# SMPS-5V.net
KiCad netlist of a schematic drawn in Altium Designer
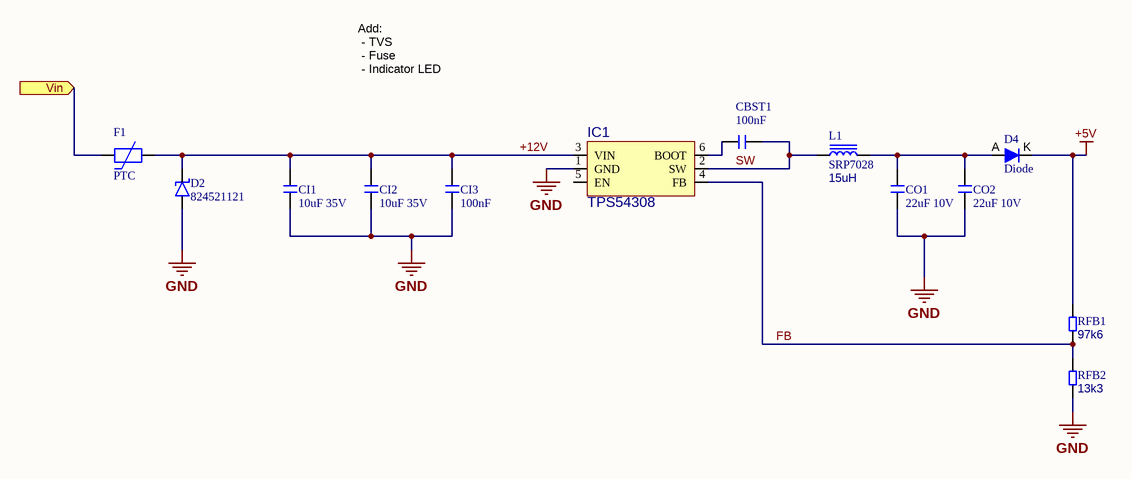
[diagram p0: SMPS-5V.SchDoc]

(export (version "E")
  (design (tool "Eeschema 10.0.6"))
  (components
    (comp (ref "CBST1")
      (value "100nF")
      (footprint "C0603_N")
      (description "Capacitor MLCC")
      (fields
        (field (name "MANUFACTURER") "Yageo")
        (field (name "MANUFACTURER PART NUMBER") "CC0603KRX7R9BB104")
      )
      (libsource (lib "wes") (part "Capacitor"))
    )
    (comp (ref "CI1")
      (value "10uF 35V")
      (footprint "C1210_N")
      (description "Capacitor MLCC")
      (fields
        (field (name "MANUFACTURER") "Yageo")
        (field (name "MANUFACTURER PART NUMBER") "CC0603KRX7R9BB104")
      )
      (libsource (lib "wes") (part "Capacitor"))
    )
    (comp (ref "CI2")
      (value "10uF 35V")
      (footprint "C1210_N")
      (description "Capacitor MLCC")
      (fields
        (field (name "MANUFACTURER") "Yageo")
        (field (name "MANUFACTURER PART NUMBER") "CC0603KRX7R9BB104")
      )
      (libsource (lib "wes") (part "Capacitor"))
    )
    (comp (ref "CI3")
      (value "100nF")
      (footprint "C0603_N")
      (description "Capacitor MLCC")
      (fields
        (field (name "MANUFACTURER") "Yageo")
        (field (name "MANUFACTURER PART NUMBER") "CC0603KRX7R9BB104")
      )
      (libsource (lib "wes") (part "Capacitor"))
    )
    (comp (ref "CO1")
      (value "22uF 10V")
      (footprint "C1210_N")
      (description "Capacitor MLCC")
      (fields
        (field (name "MANUFACTURER") "Yageo")
        (field (name "MANUFACTURER PART NUMBER") "CC0603KRX7R9BB104")
      )
      (libsource (lib "wes") (part "Capacitor"))
    )
    (comp (ref "CO2")
      (value "22uF 10V")
      (footprint "C1210_N")
      (description "Capacitor MLCC")
      (fields
        (field (name "MANUFACTURER") "Yageo")
        (field (name "MANUFACTURER PART NUMBER") "CC0603KRX7R9BB104")
      )
      (libsource (lib "wes") (part "Capacitor"))
    )
    (comp (ref "D2") (value "824521121") (footprint "DO214AC SMA") (libsource (lib "wes") (part "TVS")))
    (comp (ref "D4") (value "Diode") (footprint "SOD323F") (libsource (lib "wes") (part "Diode")))
    (comp (ref "F1")
      (value "PTC")
      (footprint "C1206_N")
      (description "PTC, Resettable Fuse")
      (libsource (lib "wes") (part "PTC"))
    )
    (comp (ref "IC1")
      (value "TPS54308")
      (footprint "SOT23")
      (description "Buck Converter")
      (libsource (lib "wes") (part "TPS54308"))
    )
    (comp (ref "L1")
      (value "SRP7028")
      (footprint "Inductor SRP7028")
      (fields (field (name "ALTIUM_VALUE") "15uH"))
      (libsource (lib "wes") (part "Inductor"))
    )
    (comp (ref "RFB1")
      (value "97k6")
      (footprint "R0603")
      (fields (field (name "Comment") "100k") (field (name "PUBLISHER") "Altium Limited"))
      (libsource (lib "wes") (part "Resistor"))
    )
    (comp (ref "RFB2")
      (value "13k3")
      (footprint "R0603")
      (fields (field (name "Comment") "13k5") (field (name "PUBLISHER") "Altium Limited"))
      (libsource (lib "wes") (part "Resistor"))
    )
  )
  (nets
    (net (code "1") (name "+5V") (class "Default")
      (node (ref "D4") (pin "K") (pinfunction "K_K") (pintype "passive"))
      (node (ref "RFB1") (pin "2") (pinfunction "2_2") (pintype "passive"))
    )
    (net (code "2") (name "/+12V") (class "Default")
      (node (ref "CI1") (pin "1") (pintype "passive"))
      (node (ref "CI2") (pin "1") (pintype "passive"))
      (node (ref "CI3") (pin "1") (pintype "passive"))
      (node (ref "D2") (pin "2") (pinfunction "2_2") (pintype "passive"))
      (node (ref "F1") (pin "2") (pinfunction "2_2") (pintype "passive"))
      (node (ref "IC1") (pin "3") (pinfunction "VIN_3") (pintype "passive"))
    )
    (net (code "3") (name "/FB") (class "Default")
      (node (ref "IC1") (pin "4") (pinfunction "FB_4") (pintype "passive"))
      (node (ref "RFB1") (pin "1") (pinfunction "1_1") (pintype "passive"))
      (node (ref "RFB2") (pin "2") (pinfunction "2_2") (pintype "passive"))
    )
    (net (code "4") (name "/SW") (class "Default")
      (node (ref "CBST1") (pin "2") (pintype "passive"))
      (node (ref "IC1") (pin "2") (pinfunction "SW_2") (pintype "passive"))
      (node (ref "L1") (pin "1") (pinfunction "1_1") (pintype "passive"))
    )
    (net (code "5") (name "/Vin") (class "Default")
      (node (ref "F1") (pin "1") (pinfunction "1_1") (pintype "passive"))
    )
    (net (code "6") (name "GND") (class "Default")
      (node (ref "CI1") (pin "2") (pintype "passive"))
      (node (ref "CI2") (pin "2") (pintype "passive"))
      (node (ref "CI3") (pin "2") (pintype "passive"))
      (node (ref "CO1") (pin "2") (pintype "passive"))
      (node (ref "CO2") (pin "2") (pintype "passive"))
      (node (ref "D2") (pin "1") (pinfunction "1_1") (pintype "passive"))
      (node (ref "IC1") (pin "1") (pinfunction "GND_1") (pintype "passive"))
      (node (ref "RFB2") (pin "1") (pinfunction "1_1") (pintype "passive"))
    )
    (net (code "7") (name "Net-(CO1-Pad1)") (class "Default")
      (node (ref "CO1") (pin "1") (pintype "passive"))
      (node (ref "CO2") (pin "1") (pintype "passive"))
      (node (ref "D4") (pin "A") (pinfunction "A_A") (pintype "passive"))
      (node (ref "L1") (pin "2") (pinfunction "2_2") (pintype "passive"))
    )
    (net (code "8") (name "Net-(IC1-BOOT)") (class "Default")
      (node (ref "CBST1") (pin "1") (pintype "passive"))
      (node (ref "IC1") (pin "6") (pinfunction "BOOT_6") (pintype "passive"))
    )
    (net (code "9") (name "unconnected-(IC1-EN-Pad5)") (class "Default")
      (node (ref "IC1") (pin "5") (pinfunction "EN_5") (pintype "passive"))
    )
  )
)
